# BLDC_Motor_Controller_2016_Rev1.net
KiCad netlist of a schematic drawn in EAGLE
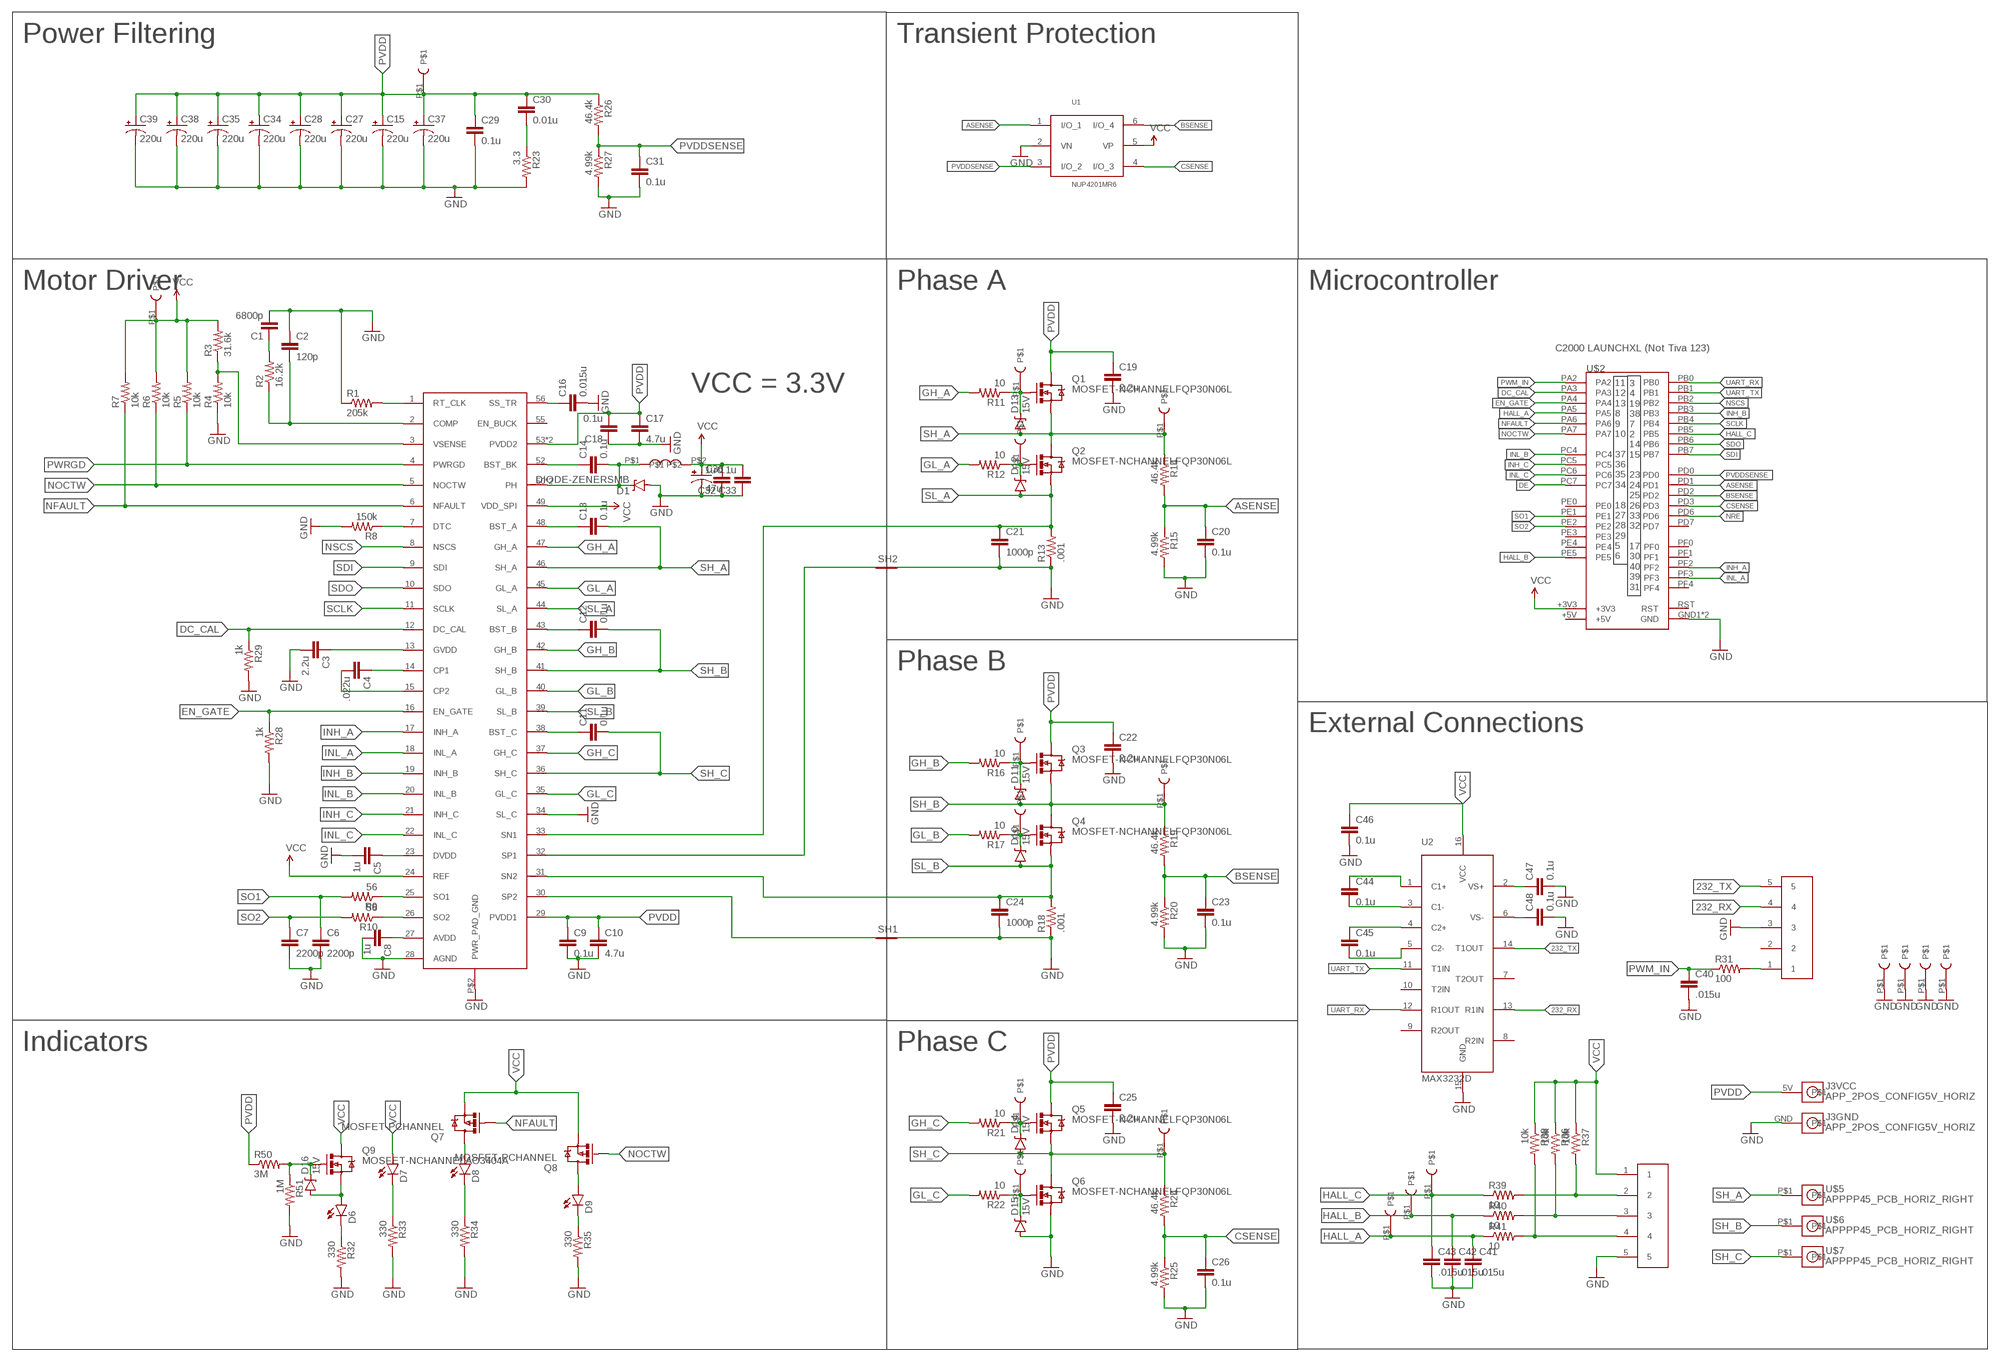
[diagram p0: schematic, sheet 1]

(export (version "E")
  (design (tool "Eeschema 10.0.6"))
  (components
    (comp (ref "C1")
      (value "6800p")
      (footprint "eagle-import:0805")
      (libsource (lib "eagle-import") (part "CAP0805"))
    )
    (comp (ref "C2")
      (value "120p")
      (footprint "eagle-import:0805")
      (libsource (lib "eagle-import") (part "CAP0805"))
    )
    (comp (ref "C3")
      (value "2.2u")
      (footprint "eagle-import:1206")
      (libsource (lib "eagle-import") (part "CAP1206"))
    )
    (comp (ref "C4")
      (value ".022u")
      (footprint "eagle-import:0805")
      (libsource (lib "eagle-import") (part "CAP0805"))
    )
    (comp (ref "C5")
      (value "1u")
      (footprint "eagle-import:0805")
      (libsource (lib "eagle-import") (part "CAP0805"))
    )
    (comp (ref "C6")
      (value "2200p")
      (footprint "eagle-import:0805")
      (libsource (lib "eagle-import") (part "CAP0805"))
    )
    (comp (ref "C7")
      (value "2200p")
      (footprint "eagle-import:0805")
      (libsource (lib "eagle-import") (part "CAP0805"))
    )
    (comp (ref "C8")
      (value "1u")
      (footprint "eagle-import:0805")
      (libsource (lib "eagle-import") (part "CAP0805"))
    )
    (comp (ref "C9")
      (value "0.1u")
      (footprint "eagle-import:0805")
      (libsource (lib "eagle-import") (part "CAP0805"))
    )
    (comp (ref "C10")
      (value "4.7u")
      (footprint "eagle-import:1206")
      (libsource (lib "eagle-import") (part "CAP1206"))
    )
    (comp (ref "C11")
      (value "0.1u")
      (footprint "eagle-import:0805")
      (libsource (lib "eagle-import") (part "CAP0805"))
    )
    (comp (ref "C12")
      (value "0.1u")
      (footprint "eagle-import:0805")
      (libsource (lib "eagle-import") (part "CAP0805"))
    )
    (comp (ref "C13")
      (value "0.1u")
      (footprint "eagle-import:0805")
      (libsource (lib "eagle-import") (part "CAP0805"))
    )
    (comp (ref "C14")
      (value "0.1u")
      (footprint "eagle-import:0805")
      (libsource (lib "eagle-import") (part "CAP0805"))
    )
    (comp (ref "C15")
      (value "220u")
      (footprint "eagle-import:CPOL-RADIAL-1000UF-25V")
      (libsource (lib "eagle-import") (part "CAP_POLPTH4"))
    )
    (comp (ref "C16")
      (value "0.015u")
      (footprint "eagle-import:0805")
      (libsource (lib "eagle-import") (part "CAP0805"))
    )
    (comp (ref "C17")
      (value "4.7u")
      (footprint "eagle-import:1206")
      (libsource (lib "eagle-import") (part "CAP1206"))
    )
    (comp (ref "C18")
      (value "0.1u")
      (footprint "eagle-import:0805")
      (libsource (lib "eagle-import") (part "CAP0805"))
    )
    (comp (ref "C19")
      (value "2.2u")
      (footprint "eagle-import:1206")
      (libsource (lib "eagle-import") (part "CAP1206"))
    )
    (comp (ref "C20")
      (value "0.1u")
      (footprint "eagle-import:0805")
      (libsource (lib "eagle-import") (part "CAP0805"))
    )
    (comp (ref "C21")
      (value "1000p")
      (footprint "eagle-import:0805")
      (libsource (lib "eagle-import") (part "CAP0805"))
    )
    (comp (ref "C22")
      (value "2.2u")
      (footprint "eagle-import:1206")
      (libsource (lib "eagle-import") (part "CAP1206"))
    )
    (comp (ref "C23")
      (value "0.1u")
      (footprint "eagle-import:0805")
      (libsource (lib "eagle-import") (part "CAP0805"))
    )
    (comp (ref "C24")
      (value "1000p")
      (footprint "eagle-import:0805")
      (libsource (lib "eagle-import") (part "CAP0805"))
    )
    (comp (ref "C25")
      (value "2.2u")
      (footprint "eagle-import:1206")
      (libsource (lib "eagle-import") (part "CAP1206"))
    )
    (comp (ref "C26")
      (value "0.1u")
      (footprint "eagle-import:0805")
      (libsource (lib "eagle-import") (part "CAP0805"))
    )
    (comp (ref "C27")
      (value "220u")
      (footprint "eagle-import:CPOL-RADIAL-1000UF-25V")
      (libsource (lib "eagle-import") (part "CAP_POLPTH4"))
    )
    (comp (ref "C28")
      (value "220u")
      (footprint "eagle-import:CPOL-RADIAL-1000UF-25V")
      (libsource (lib "eagle-import") (part "CAP_POLPTH4"))
    )
    (comp (ref "C29")
      (value "0.1u")
      (footprint "eagle-import:0805")
      (libsource (lib "eagle-import") (part "CAP0805"))
    )
    (comp (ref "C30")
      (value "0.01u")
      (footprint "eagle-import:0805")
      (libsource (lib "eagle-import") (part "CAP0805"))
    )
    (comp (ref "C31")
      (value "0.1u")
      (footprint "eagle-import:0805")
      (libsource (lib "eagle-import") (part "CAP0805"))
    )
    (comp (ref "C32")
      (value "1u")
      (footprint "eagle-import:0805")
      (libsource (lib "eagle-import") (part "CAP0805"))
    )
    (comp (ref "C33")
      (value "0.1u")
      (footprint "eagle-import:0805")
      (libsource (lib "eagle-import") (part "CAP0805"))
    )
    (comp (ref "C34")
      (value "220u")
      (footprint "eagle-import:CPOL-RADIAL-1000UF-25V")
      (libsource (lib "eagle-import") (part "CAP_POLPTH4"))
    )
    (comp (ref "C35")
      (value "220u")
      (footprint "eagle-import:CPOL-RADIAL-1000UF-25V")
      (libsource (lib "eagle-import") (part "CAP_POLPTH4"))
    )
    (comp (ref "C36")
      (value "47u")
      (footprint "eagle-import:CPOL-RADIAL-100UF-25V")
      (libsource (lib "eagle-import") (part "CAP_POLPTH1"))
    )
    (comp (ref "C37")
      (value "220u")
      (footprint "eagle-import:CPOL-RADIAL-1000UF-25V")
      (libsource (lib "eagle-import") (part "CAP_POLPTH4"))
    )
    (comp (ref "C38")
      (value "220u")
      (footprint "eagle-import:CPOL-RADIAL-1000UF-25V")
      (libsource (lib "eagle-import") (part "CAP_POLPTH4"))
    )
    (comp (ref "C39")
      (value "220u")
      (footprint "eagle-import:CPOL-RADIAL-1000UF-25V")
      (libsource (lib "eagle-import") (part "CAP_POLPTH4"))
    )
    (comp (ref "C40")
      (value ".015u")
      (footprint "eagle-import:0805")
      (libsource (lib "eagle-import") (part "CAP0805"))
    )
    (comp (ref "C41")
      (value ".015u")
      (footprint "eagle-import:0805")
      (libsource (lib "eagle-import") (part "CAP0805"))
    )
    (comp (ref "C42")
      (value ".015u")
      (footprint "eagle-import:0805")
      (libsource (lib "eagle-import") (part "CAP0805"))
    )
    (comp (ref "C43")
      (value ".015u")
      (footprint "eagle-import:0805")
      (libsource (lib "eagle-import") (part "CAP0805"))
    )
    (comp (ref "C44")
      (value "0.1u")
      (footprint "eagle-import:0805")
      (libsource (lib "eagle-import") (part "CAP0805"))
    )
    (comp (ref "C45")
      (value "0.1u")
      (footprint "eagle-import:0805")
      (libsource (lib "eagle-import") (part "CAP0805"))
    )
    (comp (ref "C46")
      (value "0.1u")
      (footprint "eagle-import:0805")
      (libsource (lib "eagle-import") (part "CAP0805"))
    )
    (comp (ref "C47")
      (value "0.1u")
      (footprint "eagle-import:0805")
      (libsource (lib "eagle-import") (part "CAP0805"))
    )
    (comp (ref "C48")
      (value "0.1u")
      (footprint "eagle-import:0805")
      (libsource (lib "eagle-import") (part "CAP0805"))
    )
    (comp (ref "D1")
      (value "DIODE-ZENERSMB")
      (footprint "eagle-import:SMB-DIODE")
      (libsource (lib "eagle-import") (part "DIODE-ZENERSMB"))
    )
    (comp (ref "D6")
      (value "LED1206")
      (footprint "eagle-import:LED-1206")
      (libsource (lib "eagle-import") (part "LED1206"))
    )
    (comp (ref "D7")
      (value "LED1206")
      (footprint "eagle-import:LED-1206")
      (libsource (lib "eagle-import") (part "LED1206"))
    )
    (comp (ref "D8")
      (value "LED1206")
      (footprint "eagle-import:LED-1206")
      (libsource (lib "eagle-import") (part "LED1206"))
    )
    (comp (ref "D9")
      (value "LED1206")
      (footprint "eagle-import:LED-1206")
      (libsource (lib "eagle-import") (part "LED1206"))
    )
    (comp (ref "D10")
      (value "15V")
      (footprint "eagle-import:SOD-323")
      (libsource (lib "eagle-import") (part "DIODE-ZENER3.3V"))
    )
    (comp (ref "D11")
      (value "15V")
      (footprint "eagle-import:SOD-323")
      (libsource (lib "eagle-import") (part "DIODE-ZENER3.3V"))
    )
    (comp (ref "D12")
      (value "15V")
      (footprint "eagle-import:SOD-323")
      (libsource (lib "eagle-import") (part "DIODE-ZENER3.3V"))
    )
    (comp (ref "D13")
      (value "15V")
      (footprint "eagle-import:SOD-323")
      (libsource (lib "eagle-import") (part "DIODE-ZENER3.3V"))
    )
    (comp (ref "D14")
      (value "15V")
      (footprint "eagle-import:SOD-323")
      (libsource (lib "eagle-import") (part "DIODE-ZENER3.3V"))
    )
    (comp (ref "D15")
      (value "15V")
      (footprint "eagle-import:SOD-323")
      (libsource (lib "eagle-import") (part "DIODE-ZENER3.3V"))
    )
    (comp (ref "D16")
      (value "15V")
      (footprint "eagle-import:SOD-323")
      (libsource (lib "eagle-import") (part "DIODE-ZENER3.3V"))
    )
    (comp (ref "J3")
      (value "APP_2POS_CONFIG5V_HORIZ")
      (footprint "eagle-import:APP45_5V_HORIZ_CONFIG")
      (libsource (lib "eagle-import") (part "APP_2POS_CONFIG5V_HORIZ"))
    )
    (comp (ref "Q1")
      (value "MOSFET-NCHANNELFQP30N06L")
      (footprint "eagle-import:TO220V")
      (libsource (lib "eagle-import") (part "MOSFET-NCHANNELFQP30N06L"))
    )
    (comp (ref "Q2")
      (value "MOSFET-NCHANNELFQP30N06L")
      (footprint "eagle-import:TO220V")
      (libsource (lib "eagle-import") (part "MOSFET-NCHANNELFQP30N06L"))
    )
    (comp (ref "Q3")
      (value "MOSFET-NCHANNELFQP30N06L")
      (footprint "eagle-import:TO220V")
      (libsource (lib "eagle-import") (part "MOSFET-NCHANNELFQP30N06L"))
    )
    (comp (ref "Q4")
      (value "MOSFET-NCHANNELFQP30N06L")
      (footprint "eagle-import:TO220V")
      (libsource (lib "eagle-import") (part "MOSFET-NCHANNELFQP30N06L"))
    )
    (comp (ref "Q5")
      (value "MOSFET-NCHANNELFQP30N06L")
      (footprint "eagle-import:TO220V")
      (libsource (lib "eagle-import") (part "MOSFET-NCHANNELFQP30N06L"))
    )
    (comp (ref "Q6")
      (value "MOSFET-NCHANNELFQP30N06L")
      (footprint "eagle-import:TO220V")
      (libsource (lib "eagle-import") (part "MOSFET-NCHANNELFQP30N06L"))
    )
    (comp (ref "Q7")
      (value "MOSFET-PCHANNEL")
      (footprint "eagle-import:SOT23-3")
      (libsource (lib "eagle-import") (part "MOSFET-PCHANNEL"))
    )
    (comp (ref "Q8")
      (value "MOSFET-PCHANNEL")
      (footprint "eagle-import:SOT23-3")
      (libsource (lib "eagle-import") (part "MOSFET-PCHANNEL"))
    )
    (comp (ref "Q9")
      (value "MOSFET-NCHANNELAO3404A")
      (footprint "eagle-import:SOT23-3")
      (libsource (lib "eagle-import") (part "MOSFET-NCHANNELAO3404A"))
    )
    (comp (ref "R1")
      (value "205k")
      (footprint "eagle-import:0805")
      (libsource (lib "eagle-import") (part "RESISTOR0805-RES"))
    )
    (comp (ref "R2")
      (value "16.2k")
      (footprint "eagle-import:0805")
      (libsource (lib "eagle-import") (part "RESISTOR0805-RES"))
    )
    (comp (ref "R3")
      (value "31.6k")
      (footprint "eagle-import:0805")
      (libsource (lib "eagle-import") (part "RESISTOR0805-RES"))
    )
    (comp (ref "R4")
      (value "10k")
      (footprint "eagle-import:0805")
      (libsource (lib "eagle-import") (part "RESISTOR0805-RES"))
    )
    (comp (ref "R5")
      (value "10k")
      (footprint "eagle-import:0805")
      (libsource (lib "eagle-import") (part "RESISTOR0805-RES"))
    )
    (comp (ref "R6")
      (value "10k")
      (footprint "eagle-import:0805")
      (libsource (lib "eagle-import") (part "RESISTOR0805-RES"))
    )
    (comp (ref "R7")
      (value "10k")
      (footprint "eagle-import:0805")
      (libsource (lib "eagle-import") (part "RESISTOR0805-RES"))
    )
    (comp (ref "R8")
      (value "150k")
      (footprint "eagle-import:0805")
      (libsource (lib "eagle-import") (part "RESISTOR0805-RES"))
    )
    (comp (ref "R9")
      (value "56")
      (footprint "eagle-import:0805")
      (libsource (lib "eagle-import") (part "RESISTOR0805-RES"))
    )
    (comp (ref "R10")
      (value "56")
      (footprint "eagle-import:0805")
      (libsource (lib "eagle-import") (part "RESISTOR0805-RES"))
    )
    (comp (ref "R11")
      (value "10")
      (footprint "eagle-import:0805")
      (libsource (lib "eagle-import") (part "RESISTOR0805-RES"))
    )
    (comp (ref "R12")
      (value "10")
      (footprint "eagle-import:0805")
      (libsource (lib "eagle-import") (part "RESISTOR0805-RES"))
    )
    (comp (ref "R13")
      (value ".001")
      (footprint "eagle-import:1206")
      (libsource (lib "eagle-import") (part "RESISTOR1206"))
    )
    (comp (ref "R14")
      (value "46.4k")
      (footprint "eagle-import:0805")
      (libsource (lib "eagle-import") (part "RESISTOR0805-RES"))
    )
    (comp (ref "R15")
      (value "4.99k")
      (footprint "eagle-import:0805")
      (libsource (lib "eagle-import") (part "RESISTOR0805-RES"))
    )
    (comp (ref "R16")
      (value "10")
      (footprint "eagle-import:0805")
      (libsource (lib "eagle-import") (part "RESISTOR0805-RES"))
    )
    (comp (ref "R17")
      (value "10")
      (footprint "eagle-import:0805")
      (libsource (lib "eagle-import") (part "RESISTOR0805-RES"))
    )
    (comp (ref "R18")
      (value ".001")
      (footprint "eagle-import:1206")
      (libsource (lib "eagle-import") (part "RESISTOR1206"))
    )
    (comp (ref "R19")
      (value "46.4k")
      (footprint "eagle-import:0805")
      (libsource (lib "eagle-import") (part "RESISTOR0805-RES"))
    )
    (comp (ref "R20")
      (value "4.99k")
      (footprint "eagle-import:0805")
      (libsource (lib "eagle-import") (part "RESISTOR0805-RES"))
    )
    (comp (ref "R21")
      (value "10")
      (footprint "eagle-import:0805")
      (libsource (lib "eagle-import") (part "RESISTOR0805-RES"))
    )
    (comp (ref "R22")
      (value "10")
      (footprint "eagle-import:0805")
      (libsource (lib "eagle-import") (part "RESISTOR0805-RES"))
    )
    (comp (ref "R23")
      (value "3.3")
      (footprint "eagle-import:0805")
      (libsource (lib "eagle-import") (part "RESISTOR0805-RES"))
    )
    (comp (ref "R24")
      (value "46.4k")
      (footprint "eagle-import:0805")
      (libsource (lib "eagle-import") (part "RESISTOR0805-RES"))
    )
    (comp (ref "R25")
      (value "4.99k")
      (footprint "eagle-import:0805")
      (libsource (lib "eagle-import") (part "RESISTOR0805-RES"))
    )
    (comp (ref "R26")
      (value "46.4k")
      (footprint "eagle-import:0805")
      (libsource (lib "eagle-import") (part "RESISTOR0805-RES"))
    )
    (comp (ref "R27")
      (value "4.99k")
      (footprint "eagle-import:0805")
      (libsource (lib "eagle-import") (part "RESISTOR0805-RES"))
    )
    (comp (ref "R28")
      (value "1k")
      (footprint "eagle-import:0805")
      (libsource (lib "eagle-import") (part "RESISTOR0805-RES"))
    )
    (comp (ref "R29")
      (value "1k")
      (footprint "eagle-import:0805")
      (libsource (lib "eagle-import") (part "RESISTOR0805-RES"))
    )
    (comp (ref "R31")
      (value "100")
      (footprint "eagle-import:0805")
      (libsource (lib "eagle-import") (part "RESISTOR0805-RES"))
    )
    (comp (ref "R32")
      (value "330")
      (footprint "eagle-import:0805")
      (libsource (lib "eagle-import") (part "RESISTOR0805-RES"))
    )
    (comp (ref "R33")
      (value "330")
      (footprint "eagle-import:0805")
      (libsource (lib "eagle-import") (part "RESISTOR0805-RES"))
    )
    (comp (ref "R34")
      (value "330")
      (footprint "eagle-import:0805")
      (libsource (lib "eagle-import") (part "RESISTOR0805-RES"))
    )
    (comp (ref "R35")
      (value "330")
      (footprint "eagle-import:0805")
      (libsource (lib "eagle-import") (part "RESISTOR0805-RES"))
    )
    (comp (ref "R36")
      (value "10k")
      (footprint "eagle-import:0805")
      (libsource (lib "eagle-import") (part "RESISTOR0805-RES"))
    )
    (comp (ref "R37")
      (value "10k")
      (footprint "eagle-import:0805")
      (libsource (lib "eagle-import") (part "RESISTOR0805-RES"))
    )
    (comp (ref "R38")
      (value "10k")
      (footprint "eagle-import:0805")
      (libsource (lib "eagle-import") (part "RESISTOR0805-RES"))
    )
    (comp (ref "R39")
      (value "10")
      (footprint "eagle-import:0805")
      (libsource (lib "eagle-import") (part "RESISTOR0805-RES"))
    )
    (comp (ref "R40")
      (value "10")
      (footprint "eagle-import:0805")
      (libsource (lib "eagle-import") (part "RESISTOR0805-RES"))
    )
    (comp (ref "R41")
      (value "10")
      (footprint "eagle-import:0805")
      (libsource (lib "eagle-import") (part "RESISTOR0805-RES"))
    )
    (comp (ref "R50")
      (value "3M")
      (footprint "eagle-import:0805")
      (libsource (lib "eagle-import") (part "RESISTOR0805-RES"))
    )
    (comp (ref "R51")
      (value "1M")
      (footprint "eagle-import:0805")
      (libsource (lib "eagle-import") (part "RESISTOR0805-RES"))
    )
    (comp (ref "SH1")
      (value "SHORT-HT5")
      (footprint "eagle-import:SHORT_TOP-50")
      (libsource (lib "eagle-import") (part "SHORT-HT5"))
    )
    (comp (ref "SH2")
      (value "SHORT-HT5")
      (footprint "eagle-import:SHORT_TOP-50")
      (libsource (lib "eagle-import") (part "SHORT-HT5"))
    )
    (comp (ref "U$1")
      (value "DRV8301")
      (footprint "eagle-import:DCA")
      (libsource (lib "eagle-import") (part "DRV8301"))
    )
    (comp (ref "U$2")
      (value "TIVA-C")
      (footprint "eagle-import:TIVA-C")
      (libsource (lib "eagle-import") (part "TIVA-C"))
    )
    (comp (ref "U$4")
      (value "5PIN")
      (footprint "eagle-import:5PIN")
      (libsource (lib "eagle-import") (part "5PIN"))
    )
    (comp (ref "U$5")
      (value "APPPP45_PCB_HORIZ_RIGHT")
      (footprint "eagle-import:APP45_PCB_HORIZ_RIGHT")
      (libsource (lib "eagle-import") (part "APPPP45_PCB_HORIZ_RIGHT"))
    )
    (comp (ref "U$6")
      (value "APPPP45_PCB_HORIZ_RIGHT")
      (footprint "eagle-import:APP45_PCB_HORIZ_RIGHT")
      (libsource (lib "eagle-import") (part "APPPP45_PCB_HORIZ_RIGHT"))
    )
    (comp (ref "U$7")
      (value "APPPP45_PCB_HORIZ_RIGHT")
      (footprint "eagle-import:APP45_PCB_HORIZ_RIGHT")
      (libsource (lib "eagle-import") (part "APPPP45_PCB_HORIZ_RIGHT"))
    )
    (comp (ref "U$8")
      (value "5PIN")
      (footprint "eagle-import:5PIN")
      (libsource (lib "eagle-import") (part "5PIN"))
    )
    (comp (ref "U$10")
      (value "TEST_POINT_0.1INDIAM")
      (footprint "eagle-import:TEST_POINT_0.1INDIAM")
      (libsource (lib "eagle-import") (part "TEST_POINT_0.1INDIAM"))
    )
    (comp (ref "U$11")
      (value "TEST_POINT_0.1INDIAM")
      (footprint "eagle-import:TEST_POINT_0.1INDIAM")
      (libsource (lib "eagle-import") (part "TEST_POINT_0.1INDIAM"))
    )
    (comp (ref "U$12")
      (value "TEST_POINT_0.1INDIAM")
      (footprint "eagle-import:TEST_POINT_0.1INDIAM")
      (libsource (lib "eagle-import") (part "TEST_POINT_0.1INDIAM"))
    )
    (comp (ref "U$14")
      (value "33u")
      (footprint "eagle-import:INDUCTOR_DR74")
      (libsource (lib "eagle-import") (part "INDUCTOR_DR74"))
    )
    (comp (ref "U$15")
      (value "TEST_POINT_0.1INDIAM")
      (footprint "eagle-import:TEST_POINT_0.1INDIAM")
      (libsource (lib "eagle-import") (part "TEST_POINT_0.1INDIAM"))
    )
    (comp (ref "U$16")
      (value "TEST_POINT_0.1INDIAM")
      (footprint "eagle-import:TEST_POINT_0.1INDIAM")
      (libsource (lib "eagle-import") (part "TEST_POINT_0.1INDIAM"))
    )
    (comp (ref "U$17")
      (value "TEST_POINT_0.1INDIAM")
      (footprint "eagle-import:TEST_POINT_0.1INDIAM")
      (libsource (lib "eagle-import") (part "TEST_POINT_0.1INDIAM"))
    )
    (comp (ref "U$18")
      (value "TEST_POINT_0.1INDIAM")
      (footprint "eagle-import:TEST_POINT_0.1INDIAM")
      (libsource (lib "eagle-import") (part "TEST_POINT_0.1INDIAM"))
    )
    (comp (ref "U$19")
      (value "TEST_POINT_0.1INDIAM")
      (footprint "eagle-import:TEST_POINT_0.1INDIAM")
      (libsource (lib "eagle-import") (part "TEST_POINT_0.1INDIAM"))
    )
    (comp (ref "U$20")
      (value "TEST_POINT_0.1INDIAM")
      (footprint "eagle-import:TEST_POINT_0.1INDIAM")
      (libsource (lib "eagle-import") (part "TEST_POINT_0.1INDIAM"))
    )
    (comp (ref "U$21")
      (value "TEST_POINT_0.1INDIAM")
      (footprint "eagle-import:TEST_POINT_0.1INDIAM")
      (libsource (lib "eagle-import") (part "TEST_POINT_0.1INDIAM"))
    )
    (comp (ref "U$22")
      (value "TEST_POINT_0.1INDIAM")
      (footprint "eagle-import:TEST_POINT_0.1INDIAM")
      (libsource (lib "eagle-import") (part "TEST_POINT_0.1INDIAM"))
    )
    (comp (ref "U$23")
      (value "TEST_POINT_0.1INDIAM")
      (footprint "eagle-import:TEST_POINT_0.1INDIAM")
      (libsource (lib "eagle-import") (part "TEST_POINT_0.1INDIAM"))
    )
    (comp (ref "U$24")
      (value "TEST_POINT_0.1INDIAM")
      (footprint "eagle-import:TEST_POINT_0.1INDIAM")
      (libsource (lib "eagle-import") (part "TEST_POINT_0.1INDIAM"))
    )
    (comp (ref "U$25")
      (value "TEST_POINT_0.1INDIAM")
      (footprint "eagle-import:TEST_POINT_0.1INDIAM")
      (libsource (lib "eagle-import") (part "TEST_POINT_0.1INDIAM"))
    )
    (comp (ref "U$26")
      (value "TEST_POINT_0.1INDIAM")
      (footprint "eagle-import:TEST_POINT_0.1INDIAM")
      (libsource (lib "eagle-import") (part "TEST_POINT_0.1INDIAM"))
    )
    (comp (ref "U$27")
      (value "TEST_POINT_0.1INDIAM")
      (footprint "eagle-import:TEST_POINT_0.1INDIAM")
      (libsource (lib "eagle-import") (part "TEST_POINT_0.1INDIAM"))
    )
    (comp (ref "U$28")
      (value "TEST_POINT_0.1INDIAM")
      (footprint "eagle-import:TEST_POINT_0.1INDIAM")
      (libsource (lib "eagle-import") (part "TEST_POINT_0.1INDIAM"))
    )
    (comp (ref "U$29")
      (value "TEST_POINT_0.1INDIAM")
      (footprint "eagle-import:TEST_POINT_0.1INDIAM")
      (libsource (lib "eagle-import") (part "TEST_POINT_0.1INDIAM"))
    )
    (comp (ref "U1")
      (value "NUP4201MR6")
      (footprint "eagle-import:TSOP-6")
      (libsource (lib "eagle-import") (part "NUP4201MR6"))
    )
    (comp (ref "U2")
      (value "MAX3232D")
      (footprint "eagle-import:SOIC16")
      (libsource (lib "eagle-import") (part "MAX232D3"))
    )
  )
  (nets
    (net (code "1") (name "/+5V") (class "Default")
      (node (ref "U$2") (pin "+5V") (pinfunction "+5V_+5V") (pintype "power_in"))
    )
    (net (code "2") (name "/RST") (class "Default")
      (node (ref "U$2") (pin "RST") (pinfunction "RST_RST") (pintype "power_in"))
    )
    (net (code "3") (name "232_RX") (class "Default")
      (node (ref "U$4") (pin "4") (pinfunction "4_4") (pintype "bidirectional"))
      (node (ref "U2") (pin "13") (pinfunction "R1IN_13") (pintype "bidirectional"))
    )
    (net (code "4") (name "232_TX") (class "Default")
      (node (ref "U$4") (pin "5") (pinfunction "5_5") (pintype "bidirectional"))
      (node (ref "U2") (pin "14") (pinfunction "T1OUT_14") (pintype "bidirectional"))
    )
    (net (code "5") (name "ASENSE") (class "Default")
      (node (ref "C20") (pin "1") (pinfunction "1_1") (pintype "passive"))
      (node (ref "R14") (pin "2") (pinfunction "2_2") (pintype "passive"))
      (node (ref "R15") (pin "1") (pinfunction "1_1") (pintype "passive"))
      (node (ref "U$2") (pin "PD1") (pinfunction "PD1_PD1") (pintype "bidirectional"))
      (node (ref "U1") (pin "1") (pinfunction "I/O_1_1") (pintype "bidirectional"))
    )
    (net (code "6") (name "BSENSE") (class "Default")
      (node (ref "C23") (pin "1") (pinfunction "1_1") (pintype "passive"))
      (node (ref "R19") (pin "2") (pinfunction "2_2") (pintype "passive"))
      (node (ref "R20") (pin "1") (pinfunction "1_1") (pintype "passive"))
      (node (ref "U$2") (pin "PD2") (pinfunction "PD2_PD2") (pintype "bidirectional"))
      (node (ref "U1") (pin "6") (pinfunction "I/O_4_6") (pintype "bidirectional"))
    )
    (net (code "7") (name "CSENSE") (class "Default")
      (node (ref "C26") (pin "1") (pinfunction "1_1") (pintype "passive"))
      (node (ref "R24") (pin "2") (pinfunction "2_2") (pintype "passive"))
      (node (ref "R25") (pin "1") (pinfunction "1_1") (pintype "passive"))
      (node (ref "U$2") (pin "PD3") (pinfunction "PD3_PD3") (pintype "bidirectional"))
      (node (ref "U1") (pin "4") (pinfunction "I/O_3_4") (pintype "bidirectional"))
    )
    (net (code "8") (name "DC_CAL") (class "Default")
      (node (ref "R29") (pin "1") (pinfunction "1_1") (pintype "passive"))
      (node (ref "U$1") (pin "12") (pinfunction "DC_CAL_12") (pintype "bidirectional"))
      (node (ref "U$2") (pin "PA3") (pinfunction "PA3_PA3") (pintype "bidirectional"))
    )
    (net (code "9") (name "DE") (class "Default")
      (node (ref "U$2") (pin "PC7") (pinfunction "PC7_PC7") (pintype "bidirectional"))
    )
    (net (code "10") (name "EN_GATE") (class "Default")
      (node (ref "R28") (pin "1") (pinfunction "1_1") (pintype "passive"))
      (node (ref "U$1") (pin "16") (pinfunction "EN_GATE_16") (pintype "bidirectional"))
      (node (ref "U$2") (pin "PA4") (pinfunction "PA4_PA4") (pintype "bidirectional"))
    )
    (net (code "11") (name "GH_A") (class "Default")
      (node (ref "R11") (pin "2") (pinfunction "2_2") (pintype "passive"))
      (node (ref "U$1") (pin "47") (pinfunction "GH_A_47") (pintype "bidirectional"))
    )
    (net (code "12") (name "GH_B") (class "Default")
      (node (ref "R16") (pin "2") (pinfunction "2_2") (pintype "passive"))
      (node (ref "U$1") (pin "42") (pinfunction "GH_B_42") (pintype "bidirectional"))
    )
    (net (code "13") (name "GH_C") (class "Default")
      (node (ref "R21") (pin "2") (pinfunction "2_2") (pintype "passive"))
      (node (ref "U$1") (pin "37") (pinfunction "GH_C_37") (pintype "bidirectional"))
    )
    (net (code "14") (name "GL_A") (class "Default")
      (node (ref "R12") (pin "2") (pinfunction "2_2") (pintype "passive"))
      (node (ref "U$1") (pin "45") (pinfunction "GL_A_45") (pintype "bidirectional"))
    )
    (net (code "15") (name "GL_B") (class "Default")
      (node (ref "R17") (pin "2") (pinfunction "2_2") (pintype "passive"))
      (node (ref "U$1") (pin "40") (pinfunction "GL_B_40") (pintype "bidirectional"))
    )
    (net (code "16") (name "GL_C") (class "Default")
      (node (ref "R22") (pin "2") (pinfunction "2_2") (pintype "passive"))
      (node (ref "U$1") (pin "35") (pinfunction "GL_C_35") (pintype "bidirectional"))
    )
    (net (code "17") (name "GND") (class "Default")
      (node (ref "C1") (pin "2") (pinfunction "2_2") (pintype "passive"))
      (node (ref "C10") (pin "2") (pinfunction "2_2") (pintype "passive"))
      (node (ref "C15") (pin "2") (pinfunction "-_2") (pintype "passive"))
      (node (ref "C16") (pin "2") (pinfunction "2_2") (pintype "passive"))
      (node (ref "C17") (pin "2") (pinfunction "2_2") (pintype "passive"))
      (node (ref "C18") (pin "1") (pinfunction "1_1") (pintype "passive"))
      (node (ref "C19") (pin "2") (pinfunction "2_2") (pintype "passive"))
      (node (ref "C2") (pin "1") (pinfunction "1_1") (pintype "passive"))
      (node (ref "C20") (pin "2") (pinfunction "2_2") (pintype "passive"))
      (node (ref "C21") (pin "2") (pinfunction "2_2") (pintype "passive"))
      (node (ref "C22") (pin "2") (pinfunction "2_2") (pintype "passive"))
      (node (ref "C23") (pin "2") (pinfunction "2_2") (pintype "passive"))
      (node (ref "C24") (pin "2") (pinfunction "2_2") (pintype "passive"))
      (node (ref "C25") (pin "2") (pinfunction "2_2") (pintype "passive"))
      (node (ref "C26") (pin "2") (pinfunction "2_2") (pintype "passive"))
      (node (ref "C27") (pin "2") (pinfunction "-_2") (pintype "passive"))
      (node (ref "C28") (pin "2") (pinfunction "-_2") (pintype "passive"))
      (node (ref "C29") (pin "2") (pinfunction "2_2") (pintype "passive"))
      (node (ref "C3") (pin "2") (pinfunction "2_2") (pintype "passive"))
      (node (ref "C31") (pin "2") (pinfunction "2_2") (pintype "passive"))
      (node (ref "C32") (pin "1") (pinfunction "1_1") (pintype "passive"))
      (node (ref "C33") (pin "1") (pinfunction "1_1") (pintype "passive"))
      (node (ref "C34") (pin "2") (pinfunction "-_2") (pintype "passive"))
      (node (ref "C35") (pin "2") (pinfunction "-_2") (pintype "passive"))
      (node (ref "C36") (pin "2") (pinfunction "-_2") (pintype "passive"))
      (node (ref "C37") (pin "2") (pinfunction "-_2") (pintype "passive"))
      (node (ref "C38") (pin "2") (pinfunction "-_2") (pintype "passive"))
      (node (ref "C39") (pin "2") (pinfunction "-_2") (pintype "passive"))
      (node (ref "C40") (pin "2") (pinfunction "2_2") (pintype "passive"))
      (node (ref "C41") (pin "2") (pinfunction "2_2") (pintype "passive"))
      (node (ref "C42") (pin "2") (pinfunction "2_2") (pintype "passive"))
      (node (ref "C43") (pin "2") (pinfunction "2_2") (pintype "passive"))
      (node (ref "C46") (pin "2") (pinfunction "2_2") (pintype "passive"))
      (node (ref "C47") (pin "2") (pinfunction "2_2") (pintype "passive"))
      (node (ref "C48") (pin "2") (pinfunction "2_2") (pintype "passive"))
      (node (ref "C5") (pin "2") (pinfunction "2_2") (pintype "passive"))
      (node (ref "C6") (pin "2") (pinfunction "2_2") (pintype "passive"))
      (node (ref "C7") (pin "2") (pinfunction "2_2") (pintype "passive"))
      (node (ref "C8") (pin "2") (pinfunction "2_2") (pintype "passive"))
      (node (ref "C9") (pin "2") (pinfunction "2_2") (pintype "passive"))
      (node (ref "D1") (pin "A") (pinfunction "A_A") (pintype "passive"))
      (node (ref "D15") (pin "A") (pinfunction "A_A") (pintype "passive"))
      (node (ref "J3") (pin "GND") (pinfunction "P$1_GND") (pintype "bidirectional"))
      (node (ref "Q6") (pin "3") (pinfunction "S_3") (pintype "passive"))
      (node (ref "R1") (pin "1") (pinfunction "1_1") (pintype "passive"))
      (node (ref "R13") (pin "1") (pinfunction "1_1") (pintype "passive"))
      (node (ref "R15") (pin "2") (pinfunction "2_2") (pintype "passive"))
      (node (ref "R18") (pin "1") (pinfunction "1_1") (pintype "passive"))
      (node (ref "R20") (pin "2") (pinfunction "2_2") (pintype "passive"))
      (node (ref "R23") (pin "2") (pinfunction "2_2") (pintype "passive"))
      (node (ref "R25") (pin "2") (pinfunction "2_2") (pintype "passive"))
      (node (ref "R27") (pin "2") (pinfunction "2_2") (pintype "passive"))
      (node (ref "R28") (pin "2") (pinfunction "2_2") (pintype "passive"))
      (node (ref "R29") (pin "2") (pinfunction "2_2") (pintype "passive"))
      (node (ref "R32") (pin "2") (pinfunction "2_2") (pintype "passive"))
      (node (ref "R33") (pin "2") (pinfunction "2_2") (pintype "passive"))
      (node (ref "R34") (pin "2") (pinfunction "2_2") (pintype "passive"))
      (node (ref "R35") (pin "2") (pinfunction "2_2") (pintype "passive"))
      (node (ref "R4") (pin "1") (pinfunction "1_1") (pintype "passive"))
      (node (ref "R51") (pin "2") (pinfunction "2_2") (pintype "passive"))
      (node (ref "R8") (pin "2") (pinfunction "2_2") (pintype "passive"))
      (node (ref "SH1") (pin "2") (pinfunction "P$2_2") (pintype "bidirectional"))
      (node (ref "SH2") (pin "2") (pinfunction "P$2_2") (pintype "bidirectional"))
      (node (ref "U$1") (pin "28") (pinfunction "AGND_28") (pintype "bidirectional"))
      (node (ref "U$1") (pin "34") (pinfunction "SL_C_34") (pintype "bidirectional"))
      (node (ref "U$1") (pin "P$2") (pinfunction "PWR_PAD_GND_P$2") (pintype "bidirectional"))
      (node (ref "U$2") (pin "GND1") (pinfunction "GND_GND1") (pintype "power_in"))
      (node (ref "U$2") (pin "GND2") (pinfunction "GND_GND2") (pintype "power_in"))
      (node (ref "U$26") (pin "P$1") (pinfunction "P$1_P$1") (pintype "bidirectional"))
      (node (ref "U$27") (pin "P$1") (pinfunction "P$1_P$1") (pintype "bidirectional"))
      (node (ref "U$28") (pin "P$1") (pinfunction "P$1_P$1") (pintype "bidirectional"))
      (node (ref "U$29") (pin "P$1") (pinfunction "P$1_P$1") (pintype "bidirectional"))
      (node (ref "U$4") (pin "3") (pinfunction "3_3") (pintype "bidirectional"))
      (node (ref "U$8") (pin "5") (pinfunction "5_5") (pintype "bidirectional"))
      (node (ref "U1") (pin "2") (pinfunction "VN_2") (pintype "bidirectional"))
      (node (ref "U2") (pin "15") (pinfunction "GND_15") (pintype "bidirectional"))
    )
    (net (code "18") (name "HALL_A") (class "Default")
      (node (ref "C41") (pin "1") (pinfunction "1_1") (pintype "passive"))
      (node (ref "R41") (pin "1") (pinfunction "1_1") (pintype "passive"))
      (node (ref "U$2") (pin "PA5") (pinfunction "PA5_PA5") (pintype "bidirectional"))
      (node (ref "U$22") (pin "P$1") (pinfunction "P$1_P$1") (pintype "bidirectional"))
    )
    (net (code "19") (name "HALL_B") (class "Default")
      (node (ref "C42") (pin "1") (pinfunction "1_1") (pintype "passive"))
      (node (ref "R40") (pin "1") (pinfunction "1_1") (pintype "passive"))
      (node (ref "U$2") (pin "PE5") (pinfunction "PE5_PE5") (pintype "bidirectional"))
      (node (ref "U$21") (pin "P$1") (pinfunction "P$1_P$1") (pintype "bidirectional"))
    )
    (net (code "20") (name "HALL_C") (class "Default")
      (node (ref "C43") (pin "1") (pinfunction "1_1") (pintype "passive"))
      (node (ref "R39") (pin "1") (pinfunction "1_1") (pintype "passive"))
      (node (ref "U$2") (pin "PB5") (pinfunction "PB5_PB5") (pintype "bidirectional"))
      (node (ref "U$23") (pin "P$1") (pinfunction "P$1_P$1") (pintype "bidirectional"))
    )
    (net (code "21") (name "INH_A") (class "Default")
      (node (ref "U$1") (pin "17") (pinfunction "INH_A_17") (pintype "bidirectional"))
      (node (ref "U$2") (pin "PF2") (pinfunction "PF2_PF2") (pintype "bidirectional"))
    )
    (net (code "22") (name "INH_B") (class "Default")
      (node (ref "U$1") (pin "19") (pinfunction "INH_B_19") (pintype "bidirectional"))
      (node (ref "U$2") (pin "PB3") (pinfunction "PB3_PB3") (pintype "bidirectional"))
    )
    (net (code "23") (name "INH_C") (class "Default")
      (node (ref "U$1") (pin "21") (pinfunction "INH_C_21") (pintype "bidirectional"))
      (node (ref "U$2") (pin "PC5") (pinfunction "PC5_PC5") (pintype "bidirectional"))
    )
    (net (code "24") (name "INL_A") (class "Default")
      (node (ref "U$1") (pin "18") (pinfunction "INL_A_18") (pintype "bidirectional"))
      (node (ref "U$2") (pin "PF3") (pinfunction "PF3_PF3") (pintype "bidirectional"))
    )
    (net (code "25") (name "INL_B") (class "Default")
      (node (ref "U$1") (pin "20") (pinfunction "INL_B_20") (pintype "bidirectional"))
      (node (ref "U$2") (pin "PC4") (pinfunction "PC4_PC4") (pintype "bidirectional"))
    )
    (net (code "26") (name "INL_C") (class "Default")
      (node (ref "U$1") (pin "22") (pinfunction "INL_C_22") (pintype "bidirectional"))
      (node (ref "U$2") (pin "PC6") (pinfunction "PC6_PC6") (pintype "bidirectional"))
    )
    (net (code "27") (name "NFAULT") (class "Default")
      (node (ref "Q7") (pin "1") (pinfunction "G_1") (pintype "passive"))
      (node (ref "R7") (pin "1") (pinfunction "1_1") (pintype "passive"))
      (node (ref "U$1") (pin "6") (pinfunction "NFAULT_6") (pintype "bidirectional"))
      (node (ref "U$2") (pin "PA6") (pinfunction "PA6_PA6") (pintype "bidirectional"))
    )
    (net (code "28") (name "NOCTW") (class "Default")
      (node (ref "Q8") (pin "1") (pinfunction "G_1") (pintype "passive"))
      (node (ref "R6") (pin "1") (pinfunction "1_1") (pintype "passive"))
      (node (ref "U$1") (pin "5") (pinfunction "NOCTW_5") (pintype "bidirectional"))
      (node (ref "U$2") (pin "PA7") (pinfunction "PA7_PA7") (pintype "bidirectional"))
    )
    (net (code "29") (name "NRE") (class "Default")
      (node (ref "U$2") (pin "PD6") (pinfunction "PD6_PD6") (pintype "bidirectional"))
    )
    (net (code "30") (name "NSCS") (class "Default")
      (node (ref "U$1") (pin "8") (pinfunction "NSCS_8") (pintype "bidirectional"))
      (node (ref "U$2") (pin "PB2") (pinfunction "PB2_PB2") (pintype "bidirectional"))
    )
    (net (code "31") (name "Net-(C1-Pad1)") (class "Default")
      (node (ref "C1") (pin "1") (pinfunction "1_1") (pintype "passive"))
      (node (ref "R2") (pin "2") (pinfunction "2_2") (pintype "passive"))
    )
    (net (code "32") (name "Net-(C14-Pad2)") (class "Default")
      (node (ref "C14") (pin "2") (pinfunction "2_2") (pintype "passive"))
      (node (ref "D1") (pin "C") (pinfunction "C_C") (pintype "passive"))
      (node (ref "U$1") (pin "50") (pinfunction "PH_50") (pintype "bidirectional"))
      (node (ref "U$1") (pin "51") (pinfunction "PH_51") (pintype "bidirectional"))
      (node (ref "U$14") (pin "P$1") (pinfunction "P$1_P$1") (pintype "bidirectional"))
    )
    (net (code "33") (name "Net-(C30-Pad2)") (class "Default")
      (node (ref "C30") (pin "2") (pinfunction "2_2") (pintype "passive"))
      (node (ref "R23") (pin "1") (pinfunction "1_1") (pintype "passive"))
    )
    (net (code "34") (name "Net-(D6-PadC)") (class "Default")
      (node (ref "D6") (pin "C") (pinfunction "C_C") (pintype "passive"))
      (node (ref "R32") (pin "1") (pinfunction "1_1") (pintype "passive"))
    )
    (net (code "35") (name "Net-(D7-PadC)") (class "Default")
      (node (ref "D7") (pin "C") (pinfunction "C_C") (pintype "passive"))
      (node (ref "R33") (pin "1") (pinfunction "1_1") (pintype "passive"))
    )
    (net (code "36") (name "Net-(D8-PadC)") (class "Default")
      (node (ref "D8") (pin "C") (pinfunction "C_C") (pintype "passive"))
      (node (ref "R34") (pin "1") (pinfunction "1_1") (pintype "passive"))
    )
    (net (code "37") (name "Net-(D9-PadC)") (class "Default")
      (node (ref "D9") (pin "C") (pinfunction "C_C") (pintype "passive"))
      (node (ref "R35") (pin "1") (pinfunction "1_1") (pintype "passive"))
    )
    (net (code "38") (name "Net-(Q1-G)") (class "Default")
      (node (ref "D13") (pin "C") (pinfunction "C_C") (pintype "passive"))
      (node (ref "Q1") (pin "1") (pinfunction "G_1") (pintype "passive"))
      (node (ref "R11") (pin "1") (pinfunction "1_1") (pintype "passive"))
      (node (ref "U$12") (pin "P$1") (pinfunction "P$1_P$1") (pintype "bidirectional"))
    )
    (net (code "39") (name "Net-(Q2-G)") (class "Default")
      (node (ref "D12") (pin "C") (pinfunction "C_C") (pintype "passive"))
      (node (ref "Q2") (pin "1") (pinfunction "G_1") (pintype "passive"))
      (node (ref "R12") (pin "1") (pinfunction "1_1") (pintype "passive"))
      (node (ref "U$15") (pin "P$1") (pinfunction "P$1_P$1") (pintype "bidirectional"))
    )
    (net (code "40") (name "Net-(Q3-G)") (class "Default")
      (node (ref "D11") (pin "C") (pinfunction "C_C") (pintype "passive"))
      (node (ref "Q3") (pin "1") (pinfunction "G_1") (pintype "passive"))
      (node (ref "R16") (pin "1") (pinfunction "1_1") (pintype "passive"))
      (node (ref "U$16") (pin "P$1") (pinfunction "P$1_P$1") (pintype "bidirectional"))
    )
    (net (code "41") (name "Net-(Q4-G)") (class "Default")
      (node (ref "D10") (pin "C") (pinfunction "C_C") (pintype "passive"))
      (node (ref "Q4") (pin "1") (pinfunction "G_1") (pintype "passive"))
      (node (ref "R17") (pin "1") (pinfunction "1_1") (pintype "passive"))
      (node (ref "U$17") (pin "P$1") (pinfunction "P$1_P$1") (pintype "bidirectional"))
    )
    (net (code "42") (name "Net-(Q5-G)") (class "Default")
      (node (ref "D14") (pin "C") (pinfunction "C_C") (pintype "passive"))
      (node (ref "Q5") (pin "1") (pinfunction "G_1") (pintype "passive"))
      (node (ref "R21") (pin "1") (pinfunction "1_1") (pintype "passive"))
      (node (ref "U$18") (pin "P$1") (pinfunction "P$1_P$1") (pintype "bidirectional"))
    )
    (net (code "43") (name "Net-(Q6-G)") (class "Default")
      (node (ref "D15") (pin "C") (pinfunction "C_C") (pintype "passive"))
      (node (ref "Q6") (pin "1") (pinfunction "G_1") (pintype "passive"))
      (node (ref "R22") (pin "1") (pinfunction "1_1") (pintype "passive"))
      (node (ref "U$19") (pin "P$1") (pinfunction "P$1_P$1") (pintype "bidirectional"))
    )
    (net (code "44") (name "Net-(Q7-D)") (class "Default")
      (node (ref "D8") (pin "A") (pinfunction "A_A") (pintype "passive"))
      (node (ref "Q7") (pin "3") (pinfunction "D_3") (pintype "passive"))
    )
    (net (code "45") (name "Net-(Q8-D)") (class "Default")
      (node (ref "D9") (pin "A") (pinfunction "A_A") (pintype "passive"))
      (node (ref "Q8") (pin "3") (pinfunction "D_3") (pintype "passive"))
    )
    (net (code "46") (name "Net-(Q9-G)") (class "Default")
      (node (ref "D16") (pin "C") (pinfunction "C_C") (pintype "passive"))
      (node (ref "Q9") (pin "1") (pinfunction "G_1") (pintype "passive"))
      (node (ref "R50") (pin "2") (pinfunction "2_2") (pintype "passive"))
      (node (ref "R51") (pin "1") (pinfunction "1_1") (pintype "passive"))
    )
    (net (code "47") (name "Net-(Q9-S)") (class "Default")
      (node (ref "D16") (pin "A") (pinfunction "A_A") (pintype "passive"))
      (node (ref "D6") (pin "A") (pinfunction "A_A") (pintype "passive"))
      (node (ref "Q9") (pin "2") (pinfunction "S_2") (pintype "passive"))
    )
    (net (code "48") (name "Net-(R31-Pad2)") (class "Default")
      (node (ref "R31") (pin "2") (pinfunction "2_2") (pintype "passive"))
      (node (ref "U$4") (pin "1") (pinfunction "1_1") (pintype "bidirectional"))
    )
    (net (code "49") (name "Net-(R36-Pad2)") (class "Default")
      (node (ref "R36") (pin "2") (pinfunction "2_2") (pintype "passive"))
      (node (ref "R40") (pin "2") (pinfunction "2_2") (pintype "passive"))
      (node (ref "U$8") (pin "3") (pinfunction "3_3") (pintype "bidirectional"))
    )
    (net (code "50") (name "Net-(R37-Pad2)") (class "Default")
      (node (ref "R37") (pin "2") (pinfunction "2_2") (pintype "passive"))
      (node (ref "R39") (pin "2") (pinfunction "2_2") (pintype "passive"))
      (node (ref "U$8") (pin "2") (pinfunction "2_2") (pintype "bidirectional"))
    )
    (net (code "51") (name "Net-(R38-Pad2)") (class "Default")
      (node (ref "R38") (pin "2") (pinfunction "2_2") (pintype "passive"))
      (node (ref "R41") (pin "2") (pinfunction "2_2") (pintype "passive"))
      (node (ref "U$8") (pin "4") (pinfunction "4_4") (pintype "bidirectional"))
    )
    (net (code "52") (name "Net-(SH1-P$1)") (class "Default")
      (node (ref "SH1") (pin "1") (pinfunction "P$1_1") (pintype "bidirectional"))
      (node (ref "U$1") (pin "30") (pinfunction "SP2_30") (pintype "bidirectional"))
    )
    (net (code "53") (name "Net-(SH2-P$1)") (class "Default")
      (node (ref "SH2") (pin "1") (pinfunction "P$1_1") (pintype "bidirectional"))
      (node (ref "U$1") (pin "32") (pinfunction "SP1_32") (pintype "bidirectional"))
    )
    (net (code "54") (name "Net-(U$1-AVDD)") (class "Default")
      (node (ref "C8") (pin "1") (pinfunction "1_1") (pintype "passive"))
      (node (ref "U$1") (pin "27") (pinfunction "AVDD_27") (pintype "bidirectional"))
    )
    (net (code "55") (name "Net-(U$1-BST_A)") (class "Default")
      (node (ref "C13") (pin "1") (pinfunction "1_1") (pintype "passive"))
      (node (ref "U$1") (pin "48") (pinfunction "BST_A_48") (pintype "bidirectional"))
    )
    (net (code "56") (name "Net-(U$1-BST_B)") (class "Default")
      (node (ref "C12") (pin "1") (pinfunction "1_1") (pintype "passive"))
      (node (ref "U$1") (pin "43") (pinfunction "BST_B_43") (pintype "bidirectional"))
    )
    (net (code "57") (name "Net-(U$1-BST_BK)") (class "Default")
      (node (ref "C14") (pin "1") (pinfunction "1_1") (pintype "passive"))
      (node (ref "U$1") (pin "52") (pinfunction "BST_BK_52") (pintype "bidirectional"))
    )
    (net (code "58") (name "Net-(U$1-BST_C)") (class "Default")
      (node (ref "C11") (pin "1") (pinfunction "1_1") (pintype "passive"))
      (node (ref "U$1") (pin "38") (pinfunction "BST_C_38") (pintype "bidirectional"))
    )
    (net (code "59") (name "Net-(U$1-COMP)") (class "Default")
      (node (ref "C2") (pin "2") (pinfunction "2_2") (pintype "passive"))
      (node (ref "R2") (pin "1") (pinfunction "1_1") (pintype "passive"))
      (node (ref "U$1") (pin "2") (pinfunction "COMP_2") (pintype "bidirectional"))
    )
    (net (code "60") (name "Net-(U$1-CP1)") (class "Default")
      (node (ref "C4") (pin "1") (pinfunction "1_1") (pintype "passive"))
      (node (ref "U$1") (pin "14") (pinfunction "CP1_14") (pintype "bidirectional"))
    )
    (net (code "61") (name "Net-(U$1-CP2)") (class "Default")
      (node (ref "C4") (pin "2") (pinfunction "2_2") (pintype "passive"))
      (node (ref "U$1") (pin "15") (pinfunction "CP2_15") (pintype "bidirectional"))
    )
    (net (code "62") (name "Net-(U$1-DTC)") (class "Default")
      (node (ref "R8") (pin "1") (pinfunction "1_1") (pintype "passive"))
      (node (ref "U$1") (pin "7") (pinfunction "DTC_7") (pintype "bidirectional"))
    )
    (net (code "63") (name "Net-(U$1-DVDD)") (class "Default")
      (node (ref "C5") (pin "1") (pinfunction "1_1") (pintype "passive"))
      (node (ref "U$1") (pin "23") (pinfunction "DVDD_23") (pintype "bidirectional"))
    )
    (net (code "64") (name "Net-(U$1-GVDD)") (class "Default")
      (node (ref "C3") (pin "1") (pinfunction "1_1") (pintype "passive"))
      (node (ref "U$1") (pin "13") (pinfunction "GVDD_13") (pintype "bidirectional"))
    )
    (net (code "65") (name "Net-(U$1-RT_CLK)") (class "Default")
      (node (ref "R1") (pin "2") (pinfunction "2_2") (pintype "passive"))
      (node (ref "U$1") (pin "1") (pinfunction "RT_CLK_1") (pintype "bidirectional"))
    )
    (net (code "66") (name "Net-(U$1-SO1)") (class "Default")
      (node (ref "R9") (pin "1") (pinfunction "1_1") (pintype "passive"))
      (node (ref "U$1") (pin "25") (pinfunction "SO1_25") (pintype "bidirectional"))
    )
    (net (code "67") (name "Net-(U$1-SO2)") (class "Default")
      (node (ref "R10") (pin "1") (pinfunction "1_1") (pintype "passive"))
      (node (ref "U$1") (pin "26") (pinfunction "SO2_26") (pintype "bidirectional"))
    )
    (net (code "68") (name "Net-(U$1-SS_TR)") (class "Default")
      (node (ref "C16") (pin "1") (pinfunction "1_1") (pintype "passive"))
      (node (ref "U$1") (pin "56") (pinfunction "SS_TR_56") (pintype "bidirectional"))
    )
    (net (code "69") (name "Net-(U$1-VSENSE)") (class "Default")
      (node (ref "R3") (pin "1") (pinfunction "1_1") (pintype "passive"))
      (node (ref "R4") (pin "2") (pinfunction "2_2") (pintype "passive"))
      (node (ref "U$1") (pin "3") (pinfunction "VSENSE_3") (pintype "bidirectional"))
    )
    (net (code "70") (name "Net-(U2-C1+)") (class "Default")
      (node (ref "C44") (pin "1") (pinfunction "1_1") (pintype "passive"))
      (node (ref "U2") (pin "1") (pinfunction "C1+_1") (pintype "bidirectional"))
    )
    (net (code "71") (name "Net-(U2-C1-)") (class "Default")
      (node (ref "C44") (pin "2") (pinfunction "2_2") (pintype "passive"))
      (node (ref "U2") (pin "3") (pinfunction "C1-_3") (pintype "bidirectional"))
    )
    (net (code "72") (name "Net-(U2-C2+)") (class "Default")
      (node (ref "C45") (pin "1") (pinfunction "1_1") (pintype "passive"))
      (node (ref "U2") (pin "4") (pinfunction "C2+_4") (pintype "bidirectional"))
    )
    (net (code "73") (name "Net-(U2-C2-)") (class "Default")
      (node (ref "C45") (pin "2") (pinfunction "2_2") (pintype "passive"))
      (node (ref "U2") (pin "5") (pinfunction "C2-_5") (pintype "bidirectional"))
    )
    (net (code "74") (name "Net-(U2-VS+)") (class "Default")
      (node (ref "C47") (pin "1") (pinfunction "1_1") (pintype "passive"))
      (node (ref "U2") (pin "2") (pinfunction "VS+_2") (pintype "bidirectional"))
    )
    (net (code "75") (name "Net-(U2-VS-)") (class "Default")
      (node (ref "C48") (pin "1") (pinfunction "1_1") (pintype "passive"))
      (node (ref "U2") (pin "6") (pinfunction "VS-_6") (pintype "bidirectional"))
    )
    (net (code "76") (name "PVDD") (class "Default")
      (node (ref "C10") (pin "1") (pinfunction "1_1") (pintype "passive"))
      (node (ref "C15") (pin "1") (pinfunction "+_1") (pintype "passive"))
      (node (ref "C17") (pin "1") (pinfunction "1_1") (pintype "passive"))
      (node (ref "C18") (pin "2") (pinfunction "2_2") (pintype "passive"))
      (node (ref "C19") (pin "1") (pinfunction "1_1") (pintype "passive"))
      (node (ref "C22") (pin "1") (pinfunction "1_1") (pintype "passive"))
      (node (ref "C25") (pin "1") (pinfunction "1_1") (pintype "passive"))
      (node (ref "C27") (pin "1") (pinfunction "+_1") (pintype "passive"))
      (node (ref "C28") (pin "1") (pinfunction "+_1") (pintype "passive"))
      (node (ref "C29") (pin "1") (pinfunction "1_1") (pintype "passive"))
      (node (ref "C30") (pin "1") (pinfunction "1_1") (pintype "passive"))
      (node (ref "C34") (pin "1") (pinfunction "+_1") (pintype "passive"))
      (node (ref "C35") (pin "1") (pinfunction "+_1") (pintype "passive"))
      (node (ref "C37") (pin "1") (pinfunction "+_1") (pintype "passive"))
      (node (ref "C38") (pin "1") (pinfunction "+_1") (pintype "passive"))
      (node (ref "C39") (pin "1") (pinfunction "+_1") (pintype "passive"))
      (node (ref "C9") (pin "1") (pinfunction "1_1") (pintype "passive"))
      (node (ref "J3") (pin "5V") (pinfunction "P$1_5V") (pintype "bidirectional"))
      (node (ref "Q1") (pin "2") (pinfunction "D_2") (pintype "passive"))
      (node (ref "Q3") (pin "2") (pinfunction "D_2") (pintype "passive"))
      (node (ref "Q5") (pin "2") (pinfunction "D_2") (pintype "passive"))
      (node (ref "R26") (pin "1") (pinfunction "1_1") (pintype "passive"))
      (node (ref "R50") (pin "1") (pinfunction "1_1") (pintype "passive"))
      (node (ref "U$1") (pin "29") (pinfunction "PVDD1_29") (pintype "bidirectional"))
      (node (ref "U$1") (pin "53") (pinfunction "PVDD2_53") (pintype "bidirectional"))
      (node (ref "U$1") (pin "54") (pinfunction "PVDD2_54") (pintype "bidirectional"))
      (node (ref "U$11") (pin "P$1") (pinfunction "P$1_P$1") (pintype "bidirectional"))
    )
    (net (code "77") (name "PVDDSENSE") (class "Default")
      (node (ref "C31") (pin "1") (pinfunction "1_1") (pintype "passive"))
      (node (ref "R26") (pin "2") (pinfunction "2_2") (pintype "passive"))
      (node (ref "R27") (pin "1") (pinfunction "1_1") (pintype "passive"))
      (node (ref "U$2") (pin "PD0") (pinfunction "PD0_PD0") (pintype "bidirectional"))
      (node (ref "U1") (pin "3") (pinfunction "I/O_2_3") (pintype "bidirectional"))
    )
    (net (code "78") (name "PWM_IN") (class "Default")
      (node (ref "C40") (pin "1") (pinfunction "1_1") (pintype "passive"))
      (node (ref "R31") (pin "1") (pinfunction "1_1") (pintype "passive"))
      (node (ref "U$2") (pin "PA2") (pinfunction "PA2_PA2") (pintype "bidirectional"))
    )
    (net (code "79") (name "PWRGD") (class "Default")
      (node (ref "R5") (pin "1") (pinfunction "1_1") (pintype "passive"))
      (node (ref "U$1") (pin "4") (pinfunction "PWRGD_4") (pintype "bidirectional"))
    )
    (net (code "80") (name "SCLK") (class "Default")
      (node (ref "U$1") (pin "11") (pinfunction "SCLK_11") (pintype "bidirectional"))
      (node (ref "U$2") (pin "PB4") (pinfunction "PB4_PB4") (pintype "bidirectional"))
    )
    (net (code "81") (name "SDI") (class "Default")
      (node (ref "U$1") (pin "9") (pinfunction "SDI_9") (pintype "bidirectional"))
      (node (ref "U$2") (pin "PB7") (pinfunction "PB7_PB7") (pintype "bidirectional"))
    )
    (net (code "82") (name "SDO") (class "Default")
      (node (ref "U$1") (pin "10") (pinfunction "SDO_10") (pintype "bidirectional"))
      (node (ref "U$2") (pin "PB6") (pinfunction "PB6_PB6") (pintype "bidirectional"))
    )
    (net (code "83") (name "SH_A") (class "Default")
      (node (ref "C13") (pin "2") (pinfunction "2_2") (pintype "passive"))
      (node (ref "D13") (pin "A") (pinfunction "A_A") (pintype "passive"))
      (node (ref "Q1") (pin "3") (pinfunction "S_3") (pintype "passive"))
      (node (ref "Q2") (pin "2") (pinfunction "D_2") (pintype "passive"))
      (node (ref "R14") (pin "1") (pinfunction "1_1") (pintype "passive"))
      (node (ref "U$1") (pin "46") (pinfunction "SH_A_46") (pintype "bidirectional"))
      (node (ref "U$25") (pin "P$1") (pinfunction "P$1_P$1") (pintype "bidirectional"))
      (node (ref "U$5") (pin "P$1") (pinfunction "P$1_P$1") (pintype "bidirectional"))
    )
    (net (code "84") (name "SH_B") (class "Default")
      (node (ref "C12") (pin "2") (pinfunction "2_2") (pintype "passive"))
      (node (ref "D11") (pin "A") (pinfunction "A_A") (pintype "passive"))
      (node (ref "Q3") (pin "3") (pinfunction "S_3") (pintype "passive"))
      (node (ref "Q4") (pin "2") (pinfunction "D_2") (pintype "passive"))
      (node (ref "R19") (pin "1") (pinfunction "1_1") (pintype "passive"))
      (node (ref "U$1") (pin "41") (pinfunction "SH_B_41") (pintype "bidirectional"))
      (node (ref "U$24") (pin "P$1") (pinfunction "P$1_P$1") (pintype "bidirectional"))
      (node (ref "U$6") (pin "P$1") (pinfunction "P$1_P$1") (pintype "bidirectional"))
    )
    (net (code "85") (name "SH_C") (class "Default")
      (node (ref "C11") (pin "2") (pinfunction "2_2") (pintype "passive"))
      (node (ref "D14") (pin "A") (pinfunction "A_A") (pintype "passive"))
      (node (ref "Q5") (pin "3") (pinfunction "S_3") (pintype "passive"))
      (node (ref "Q6") (pin "2") (pinfunction "D_2") (pintype "passive"))
      (node (ref "R24") (pin "1") (pinfunction "1_1") (pintype "passive"))
      (node (ref "U$1") (pin "36") (pinfunction "SH_C_36") (pintype "bidirectional"))
      (node (ref "U$20") (pin "P$1") (pinfunction "P$1_P$1") (pintype "bidirectional"))
      (node (ref "U$7") (pin "P$1") (pinfunction "P$1_P$1") (pintype "bidirectional"))
    )
    (net (code "86") (name "SL_A") (class "Default")
      (node (ref "C21") (pin "1") (pinfunction "1_1") (pintype "passive"))
      (node (ref "D12") (pin "A") (pinfunction "A_A") (pintype "passive"))
      (node (ref "Q2") (pin "3") (pinfunction "S_3") (pintype "passive"))
      (node (ref "R13") (pin "2") (pinfunction "2_2") (pintype "passive"))
      (node (ref "U$1") (pin "33") (pinfunction "SN1_33") (pintype "bidirectional"))
      (node (ref "U$1") (pin "44") (pinfunction "SL_A_44") (pintype "bidirectional"))
    )
    (net (code "87") (name "SL_B") (class "Default")
      (node (ref "C24") (pin "1") (pinfunction "1_1") (pintype "passive"))
      (node (ref "D10") (pin "A") (pinfunction "A_A") (pintype "passive"))
      (node (ref "Q4") (pin "3") (pinfunction "S_3") (pintype "passive"))
      (node (ref "R18") (pin "2") (pinfunction "2_2") (pintype "passive"))
      (node (ref "U$1") (pin "31") (pinfunction "SN2_31") (pintype "bidirectional"))
      (node (ref "U$1") (pin "39") (pinfunction "SL_B_39") (pintype "bidirectional"))
    )
    (net (code "88") (name "SO1") (class "Default")
      (node (ref "C6") (pin "1") (pinfunction "1_1") (pintype "passive"))
      (node (ref "R9") (pin "2") (pinfunction "2_2") (pintype "passive"))
      (node (ref "U$2") (pin "PE1") (pinfunction "PE1_PE1") (pintype "bidirectional"))
    )
    (net (code "89") (name "SO2") (class "Default")
      (node (ref "C7") (pin "1") (pinfunction "1_1") (pintype "passive"))
      (node (ref "R10") (pin "2") (pinfunction "2_2") (pintype "passive"))
      (node (ref "U$2") (pin "PE2") (pinfunction "PE2_PE2") (pintype "bidirectional"))
    )
    (net (code "90") (name "UART_RX") (class "Default")
      (node (ref "U$2") (pin "PB0") (pinfunction "PB0_PB0") (pintype "bidirectional"))
      (node (ref "U2") (pin "12") (pinfunction "R1OUT_12") (pintype "bidirectional"))
    )
    (net (code "91") (name "UART_TX") (class "Default")
      (node (ref "U$2") (pin "PB1") (pinfunction "PB1_PB1") (pintype "bidirectional"))
      (node (ref "U2") (pin "11") (pinfunction "T1IN_11") (pintype "bidirectional"))
    )
    (net (code "92") (name "VCC") (class "Default")
      (node (ref "C32") (pin "2") (pinfunction "2_2") (pintype "passive"))
      (node (ref "C33") (pin "2") (pinfunction "2_2") (pintype "passive"))
      (node (ref "C36") (pin "1") (pinfunction "+_1") (pintype "passive"))
      (node (ref "C46") (pin "1") (pinfunction "1_1") (pintype "passive"))
      (node (ref "D7") (pin "A") (pinfunction "A_A") (pintype "passive"))
      (node (ref "Q7") (pin "2") (pinfunction "S_2") (pintype "passive"))
      (node (ref "Q8") (pin "2") (pinfunction "S_2") (pintype "passive"))
      (node (ref "Q9") (pin "3") (pinfunction "D_3") (pintype "passive"))
      (node (ref "R3") (pin "2") (pinfunction "2_2") (pintype "passive"))
      (node (ref "R36") (pin "1") (pinfunction "1_1") (pintype "passive"))
      (node (ref "R37") (pin "1") (pinfunction "1_1") (pintype "passive"))
      (node (ref "R38") (pin "1") (pinfunction "1_1") (pintype "passive"))
      (node (ref "R5") (pin "2") (pinfunction "2_2") (pintype "passive"))
      (node (ref "R6") (pin "2") (pinfunction "2_2") (pintype "passive"))
      (node (ref "R7") (pin "2") (pinfunction "2_2") (pintype "passive"))
      (node (ref "U$1") (pin "24") (pinfunction "REF_24") (pintype "bidirectional"))
      (node (ref "U$1") (pin "49") (pinfunction "VDD_SPI_49") (pintype "bidirectional"))
      (node (ref "U$10") (pin "P$1") (pinfunction "P$1_P$1") (pintype "bidirectional"))
      (node (ref "U$14") (pin "P$2") (pinfunction "P$2_P$2") (pintype "bidirectional"))
      (node (ref "U$2") (pin "+3V3") (pinfunction "+3V3_+3V3") (pintype "power_in"))
      (node (ref "U$8") (pin "1") (pinfunction "1_1") (pintype "bidirectional"))
      (node (ref "U1") (pin "5") (pinfunction "VP_5") (pintype "bidirectional"))
      (node (ref "U2") (pin "16") (pinfunction "VCC_16") (pintype "bidirectional"))
    )
    (net (code "93") (name "unconnected-(U$1-EN_BUCK-Pad55)") (class "Default")
      (node (ref "U$1") (pin "55") (pinfunction "EN_BUCK_55") (pintype "bidirectional"))
    )
    (net (code "94") (name "unconnected-(U$2-PadPD7)") (class "Default")
      (node (ref "U$2") (pin "PD7") (pinfunction "PD7_PD7") (pintype "bidirectional"))
    )
    (net (code "95") (name "unconnected-(U$2-PadPE0)") (class "Default")
      (node (ref "U$2") (pin "PE0") (pinfunction "PE0_PE0") (pintype "bidirectional"))
    )
    (net (code "96") (name "unconnected-(U$2-PadPE3)") (class "Default")
      (node (ref "U$2") (pin "PE3") (pinfunction "PE3_PE3") (pintype "bidirectional"))
    )
    (net (code "97") (name "unconnected-(U$2-PadPE4)") (class "Default")
      (node (ref "U$2") (pin "PE4") (pinfunction "PE4_PE4") (pintype "bidirectional"))
    )
    (net (code "98") (name "unconnected-(U$2-PadPF0)") (class "Default")
      (node (ref "U$2") (pin "PF0") (pinfunction "PF0_PF0") (pintype "bidirectional"))
    )
    (net (code "99") (name "unconnected-(U$2-PadPF1)") (class "Default")
      (node (ref "U$2") (pin "PF1") (pinfunction "PF1_PF1") (pintype "bidirectional"))
    )
    (net (code "100") (name "unconnected-(U$2-PadPF4)") (class "Default")
      (node (ref "U$2") (pin "PF4") (pinfunction "PF4_PF4") (pintype "bidirectional"))
    )
    (net (code "101") (name "unconnected-(U$4-Pad2)") (class "Default")
      (node (ref "U$4") (pin "2") (pinfunction "2_2") (pintype "bidirectional"))
    )
    (net (code "102") (name "unconnected-(U2-R2IN-Pad8)") (class "Default")
      (node (ref "U2") (pin "8") (pinfunction "R2IN_8") (pintype "bidirectional"))
    )
    (net (code "103") (name "unconnected-(U2-R2OUT-Pad9)") (class "Default")
      (node (ref "U2") (pin "9") (pinfunction "R2OUT_9") (pintype "bidirectional"))
    )
    (net (code "104") (name "unconnected-(U2-T2IN-Pad10)") (class "Default")
      (node (ref "U2") (pin "10") (pinfunction "T2IN_10") (pintype "bidirectional"))
    )
    (net (code "105") (name "unconnected-(U2-T2OUT-Pad7)") (class "Default")
      (node (ref "U2") (pin "7") (pinfunction "T2OUT_7") (pintype "bidirectional"))
    )
  )
)
